# MCU.net
KiCad netlist of a schematic drawn in Altium Designer
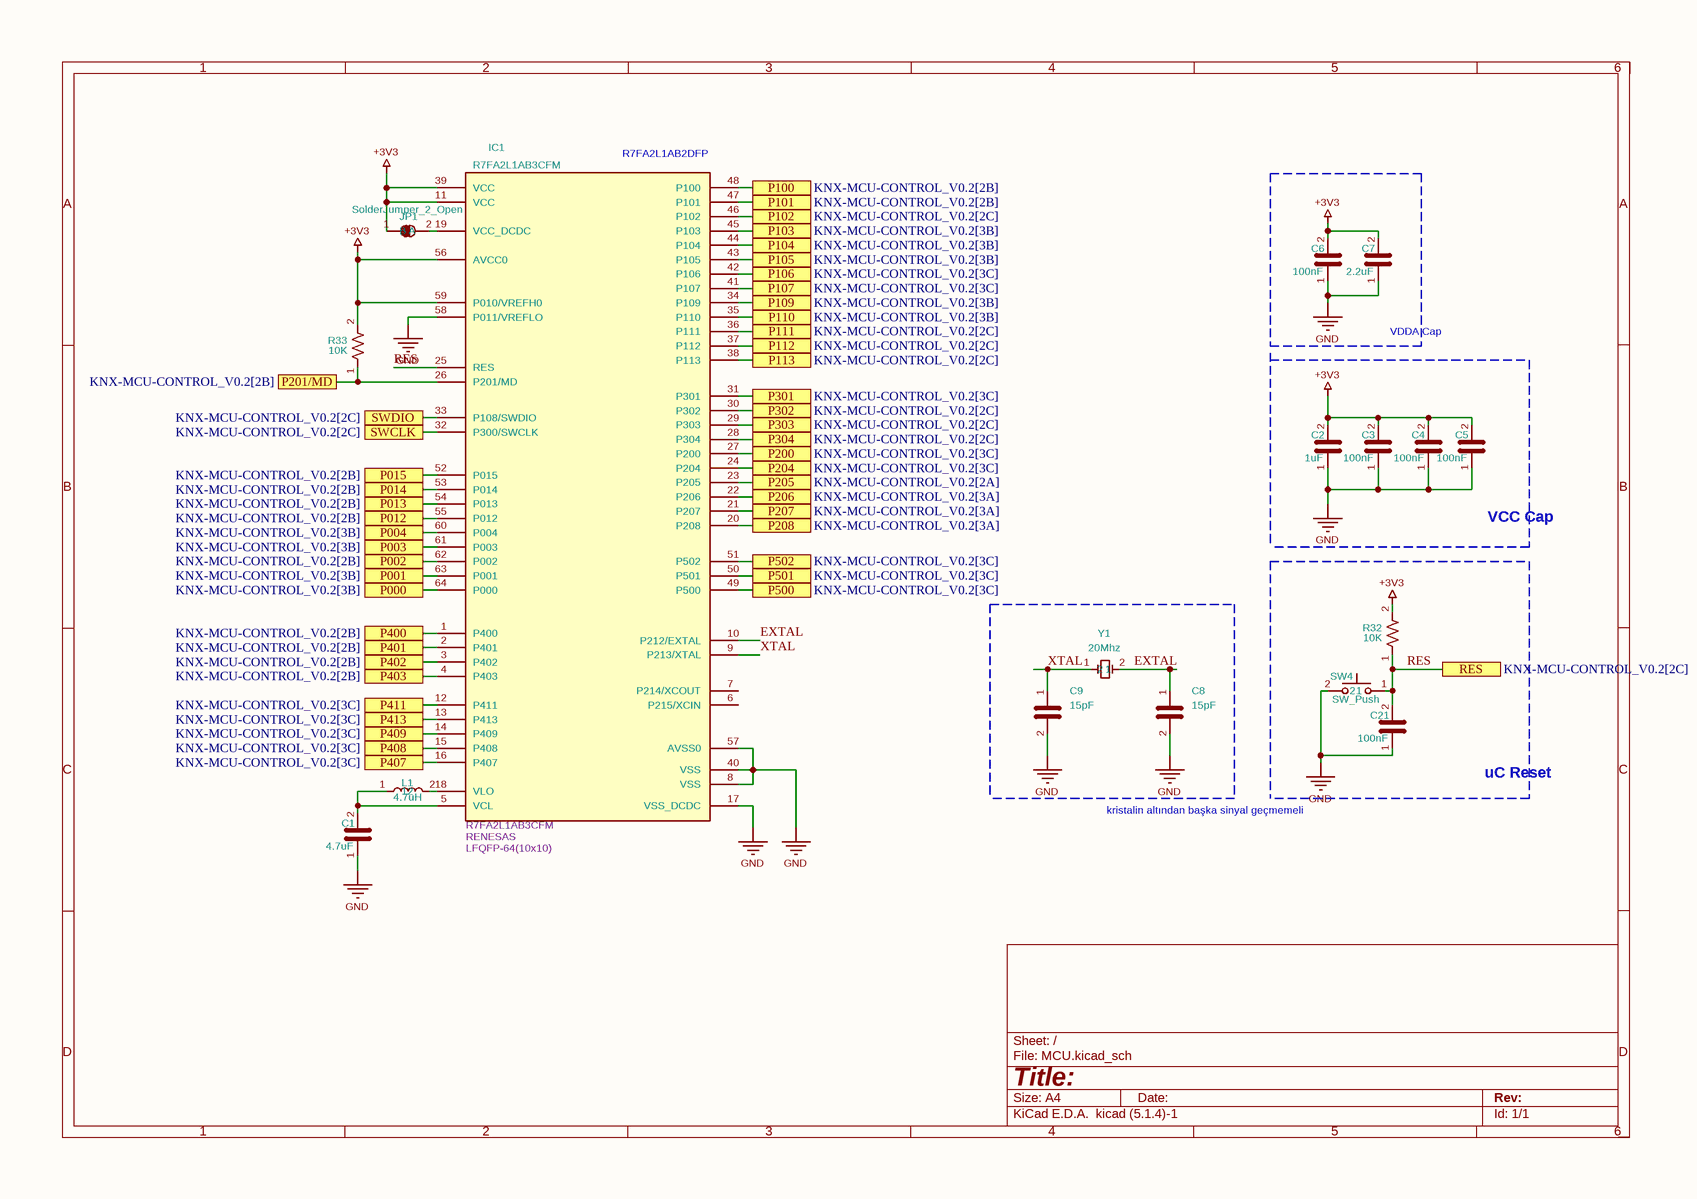
[diagram p0: MCU.SchDoc]

(export (version "E")
  (design (tool "Eeschema 10.0.6"))
  (components
    (comp (ref "C1")
      (value "4.7uF")
      (footprint "C_0603_1608Metric")
      (fields
        (field (name "MANUFACTURER PART NUMBER") "CL10B475KQ8NQNC")
        (field (name "MANUFACTURER") "Samsung Electro-Mechanics")
      )
      (libsource (lib "*") (part "C_3"))
    )
    (comp (ref "C2")
      (value "1uF")
      (footprint "C_0603_1608Metric")
      (fields
        (field (name "MANUFACTURER PART NUMBER") "CL10B105KP8NNNC")
        (field (name "MANUFACTURER") "Samsung Electro-Mechanics")
      )
      (libsource (lib "*") (part "C_3"))
    )
    (comp (ref "C3")
      (value "100nF")
      (footprint "C_0603_1608Metric")
      (fields
        (field (name "MANUFACTURER PART NUMBER") "CC0603KRX7R9BB104")
        (field (name "MANUFACTURER") "YAGEO")
      )
      (libsource (lib "*") (part "C_3"))
    )
    (comp (ref "C4")
      (value "100nF")
      (footprint "C_0603_1608Metric")
      (fields
        (field (name "MANUFACTURER PART NUMBER") "CC0603KRX7R9BB104")
        (field (name "MANUFACTURER") "YAGEO")
      )
      (libsource (lib "*") (part "C_3"))
    )
    (comp (ref "C5")
      (value "100nF")
      (footprint "C_0603_1608Metric")
      (fields
        (field (name "MANUFACTURER PART NUMBER") "CC0603KRX7R9BB104")
        (field (name "MANUFACTURER") "YAGEO")
      )
      (libsource (lib "*") (part "C_3"))
    )
    (comp (ref "C6")
      (value "100nF")
      (footprint "C_0603_1608Metric")
      (fields
        (field (name "MANUFACTURER PART NUMBER") "CC0603KRX7R9BB104")
        (field (name "MANUFACTURER") "YAGEO")
      )
      (libsource (lib "*") (part "C_3"))
    )
    (comp (ref "C7")
      (value "2.2uF")
      (footprint "C_0603_1608Metric")
      (fields
        (field (name "MANUFACTURER PART NUMBER") "CL10B225KP8NNNC")
        (field (name "MANUFACTURER") "Samsung Electro-Mechanics")
      )
      (libsource (lib "*") (part "C_3"))
    )
    (comp (ref "C8")
      (value "15pF")
      (footprint "C_0603_1608Metric")
      (fields
        (field (name "MANUFACTURER PART NUMBER") "CL10C150JB8NNNC")
        (field (name "MANUFACTURER") "Samsung Electro-Mechanics")
      )
      (libsource (lib "SparkFun-Capacitor") (part "20pF_0402_50V_5%"))
    )
    (comp (ref "C9")
      (value "15pF")
      (footprint "C_0603_1608Metric")
      (fields
        (field (name "MANUFACTURER PART NUMBER") "CL10C150JB8NNNC")
        (field (name "MANUFACTURER") "Samsung Electro-Mechanics")
      )
      (libsource (lib "SparkFun-Capacitor") (part "20pF_0402_50V_5%"))
    )
    (comp (ref "C21")
      (value "100nF")
      (footprint "C_0603_1608Metric")
      (fields
        (field (name "MANUFACTURER PART NUMBER") "CC0603KRX7R9BB104")
        (field (name "MANUFACTURER") "YAGEO")
      )
      (libsource (lib "*") (part "C_3"))
    )
    (comp (ref "IC1")
      (value "R7FA2L1AB3CFM")
      (footprint "LQFP-64_10x10mm_P0.5mm")
      (fields
        (field (name "MANUFACTURER PART NUMBER") "R7FA2L1AB3CFM")
        (field (name "MANUFACTURER") "RENESAS")
        (field (name "PACKAGE") "LFQFP-64(10x10)")
      )
      (libsource (lib "Me_Library") (part "R7FA2L1AB3CFM"))
    )
    (comp (ref "JP1")
      (value "SolderJumper_2_Open")
      (footprint "SolderJumper-2_P1.3mm_Open_TrianglePad1.0x1.5mm")
      (libsource (lib "Jumper") (part "SolderJumper_2_Open"))
    )
    (comp (ref "L1")
      (value "4.7uH")
      (footprint "L_APV_ANR5012")
      (fields (field (name "MANUFACTURER") "VIKING") (field (name "MANUFACTURER PART NUMBER") "PCD0302MT4R7"))
      (libsource (lib "Device") (part "L"))
    )
    (comp (ref "R32")
      (value "10K")
      (footprint "R_0603_1608Metric")
      (fields (field (name "MANUFACTURER PART NUMBER") "FRC0603J103TS") (field (name "MANUFACTURER") "FOJAN"))
      (libsource (lib "Device") (part "R_US"))
    )
    (comp (ref "R33")
      (value "10K")
      (footprint "R_0603_1608Metric")
      (fields (field (name "MANUFACTURER PART NUMBER") "FRC0603J103TS") (field (name "MANUFACTURER") "FOJAN"))
      (libsource (lib "Device") (part "R_US"))
    )
    (comp (ref "SW4")
      (value "SW_Push")
      (footprint "SW_SPST_CK_RS282G05A3")
      (description "SWITCH TACTILE SPST 250gf SMD")
      (fields
        (field (name "MANUFACTURER PART NUMBER") "HX 3x6x2.5A-2.5N")
        (field (name "MANUFACTURER") "hanxia")
      )
      (libsource (lib "Switch") (part "SW_Push"))
    )
    (comp (ref "Y1")
      (value "20Mhz")
      (footprint "Crystal_SMD_SeikoEpson_FA238-4Pin_3.2x2.5mm")
      (fields
        (field (name "MANUFACTURER PART NUMBER") "FL3P2X2P5SSC")
        (field (name "MANUFACTURER") "RALTRON")
      )
      (libsource (lib "SparkFun-Clock") (part "Crystal"))
    )
  )
  (nets
    (net (code "1") (name "+3V3") (class "Default")
      (node (ref "C2") (pin "2") (pinfunction "2_2") (pintype "passive"))
      (node (ref "C3") (pin "2") (pinfunction "2_2") (pintype "passive"))
      (node (ref "C4") (pin "2") (pinfunction "2_2") (pintype "passive"))
      (node (ref "C5") (pin "2") (pinfunction "2_2") (pintype "passive"))
      (node (ref "C6") (pin "2") (pinfunction "2_2") (pintype "passive"))
      (node (ref "C7") (pin "2") (pinfunction "2_2") (pintype "passive"))
      (node (ref "IC1") (pin "11") (pinfunction "VCC_11") (pintype "passive"))
      (node (ref "IC1") (pin "39") (pinfunction "VCC_39") (pintype "passive"))
      (node (ref "IC1") (pin "56") (pinfunction "AVCC0_56") (pintype "passive"))
      (node (ref "IC1") (pin "59") (pinfunction "P010/VREFH0_59") (pintype "passive"))
      (node (ref "JP1") (pin "1") (pinfunction "A_1") (pintype "passive"))
      (node (ref "R32") (pin "2") (pinfunction "2_2") (pintype "passive"))
      (node (ref "R33") (pin "2") (pinfunction "2_2") (pintype "passive"))
    )
    (net (code "2") (name "/EXTAL") (class "Default")
      (node (ref "C8") (pin "1") (pinfunction "1_1") (pintype "passive"))
      (node (ref "IC1") (pin "10") (pinfunction "P212/EXTAL_10") (pintype "passive"))
      (node (ref "Y1") (pin "2") (pinfunction "2_2") (pintype "passive"))
    )
    (net (code "3") (name "/P000") (class "Default")
      (node (ref "IC1") (pin "64") (pinfunction "P000_64") (pintype "passive"))
    )
    (net (code "4") (name "/P001") (class "Default")
      (node (ref "IC1") (pin "63") (pinfunction "P001_63") (pintype "passive"))
    )
    (net (code "5") (name "/P002") (class "Default")
      (node (ref "IC1") (pin "62") (pinfunction "P002_62") (pintype "passive"))
    )
    (net (code "6") (name "/P003") (class "Default")
      (node (ref "IC1") (pin "61") (pinfunction "P003_61") (pintype "passive"))
    )
    (net (code "7") (name "/P004") (class "Default")
      (node (ref "IC1") (pin "60") (pinfunction "P004_60") (pintype "passive"))
    )
    (net (code "8") (name "/P012") (class "Default")
      (node (ref "IC1") (pin "55") (pinfunction "P012_55") (pintype "passive"))
    )
    (net (code "9") (name "/P013") (class "Default")
      (node (ref "IC1") (pin "54") (pinfunction "P013_54") (pintype "passive"))
    )
    (net (code "10") (name "/P014") (class "Default")
      (node (ref "IC1") (pin "53") (pinfunction "P014_53") (pintype "passive"))
    )
    (net (code "11") (name "/P015") (class "Default")
      (node (ref "IC1") (pin "52") (pinfunction "P015_52") (pintype "passive"))
    )
    (net (code "12") (name "/P100") (class "Default")
      (node (ref "IC1") (pin "48") (pinfunction "P100_48") (pintype "passive"))
    )
    (net (code "13") (name "/P101") (class "Default")
      (node (ref "IC1") (pin "47") (pinfunction "P101_47") (pintype "passive"))
    )
    (net (code "14") (name "/P102") (class "Default")
      (node (ref "IC1") (pin "46") (pinfunction "P102_46") (pintype "passive"))
    )
    (net (code "15") (name "/P103") (class "Default")
      (node (ref "IC1") (pin "45") (pinfunction "P103_45") (pintype "passive"))
    )
    (net (code "16") (name "/P104") (class "Default")
      (node (ref "IC1") (pin "44") (pinfunction "P104_44") (pintype "passive"))
    )
    (net (code "17") (name "/P105") (class "Default")
      (node (ref "IC1") (pin "43") (pinfunction "P105_43") (pintype "passive"))
    )
    (net (code "18") (name "/P106") (class "Default")
      (node (ref "IC1") (pin "42") (pinfunction "P106_42") (pintype "passive"))
    )
    (net (code "19") (name "/P107") (class "Default")
      (node (ref "IC1") (pin "41") (pinfunction "P107_41") (pintype "passive"))
    )
    (net (code "20") (name "/P109") (class "Default")
      (node (ref "IC1") (pin "34") (pinfunction "P109_34") (pintype "passive"))
    )
    (net (code "21") (name "/P110") (class "Default")
      (node (ref "IC1") (pin "35") (pinfunction "P110_35") (pintype "passive"))
    )
    (net (code "22") (name "/P111") (class "Default")
      (node (ref "IC1") (pin "36") (pinfunction "P111_36") (pintype "passive"))
    )
    (net (code "23") (name "/P112") (class "Default")
      (node (ref "IC1") (pin "37") (pinfunction "P112_37") (pintype "passive"))
    )
    (net (code "24") (name "/P113") (class "Default")
      (node (ref "IC1") (pin "38") (pinfunction "P113_38") (pintype "passive"))
    )
    (net (code "25") (name "/P200") (class "Default")
      (node (ref "IC1") (pin "27") (pinfunction "P200_27") (pintype "passive"))
    )
    (net (code "26") (name "/P201{slash}MD") (class "Default")
      (node (ref "IC1") (pin "26") (pinfunction "P201/MD_26") (pintype "passive"))
      (node (ref "R33") (pin "1") (pinfunction "1_1") (pintype "passive"))
    )
    (net (code "27") (name "/P204") (class "Default")
      (node (ref "IC1") (pin "24") (pinfunction "P204_24") (pintype "passive"))
    )
    (net (code "28") (name "/P205") (class "Default")
      (node (ref "IC1") (pin "23") (pinfunction "P205_23") (pintype "passive"))
    )
    (net (code "29") (name "/P206") (class "Default")
      (node (ref "IC1") (pin "22") (pinfunction "P206_22") (pintype "passive"))
    )
    (net (code "30") (name "/P207") (class "Default")
      (node (ref "IC1") (pin "21") (pinfunction "P207_21") (pintype "passive"))
    )
    (net (code "31") (name "/P208") (class "Default")
      (node (ref "IC1") (pin "20") (pinfunction "P208_20") (pintype "passive"))
    )
    (net (code "32") (name "/P301") (class "Default")
      (node (ref "IC1") (pin "31") (pinfunction "P301_31") (pintype "passive"))
    )
    (net (code "33") (name "/P302") (class "Default")
      (node (ref "IC1") (pin "30") (pinfunction "P302_30") (pintype "passive"))
    )
    (net (code "34") (name "/P303") (class "Default")
      (node (ref "IC1") (pin "29") (pinfunction "P303_29") (pintype "passive"))
    )
    (net (code "35") (name "/P304") (class "Default")
      (node (ref "IC1") (pin "28") (pinfunction "P304_28") (pintype "passive"))
    )
    (net (code "36") (name "/P400") (class "Default")
      (node (ref "IC1") (pin "1") (pinfunction "P400_1") (pintype "passive"))
    )
    (net (code "37") (name "/P401") (class "Default")
      (node (ref "IC1") (pin "2") (pinfunction "P401_2") (pintype "passive"))
    )
    (net (code "38") (name "/P402") (class "Default")
      (node (ref "IC1") (pin "3") (pinfunction "P402_3") (pintype "passive"))
    )
    (net (code "39") (name "/P403") (class "Default")
      (node (ref "IC1") (pin "4") (pinfunction "P403_4") (pintype "passive"))
    )
    (net (code "40") (name "/P407") (class "Default")
      (node (ref "IC1") (pin "16") (pinfunction "P407_16") (pintype "passive"))
    )
    (net (code "41") (name "/P408") (class "Default")
      (node (ref "IC1") (pin "15") (pinfunction "P408_15") (pintype "passive"))
    )
    (net (code "42") (name "/P409") (class "Default")
      (node (ref "IC1") (pin "14") (pinfunction "P409_14") (pintype "passive"))
    )
    (net (code "43") (name "/P411") (class "Default")
      (node (ref "IC1") (pin "12") (pinfunction "P411_12") (pintype "passive"))
    )
    (net (code "44") (name "/P413") (class "Default")
      (node (ref "IC1") (pin "13") (pinfunction "P413_13") (pintype "passive"))
    )
    (net (code "45") (name "/P500") (class "Default")
      (node (ref "IC1") (pin "49") (pinfunction "P500_49") (pintype "passive"))
    )
    (net (code "46") (name "/P501") (class "Default")
      (node (ref "IC1") (pin "50") (pinfunction "P501_50") (pintype "passive"))
    )
    (net (code "47") (name "/P502") (class "Default")
      (node (ref "IC1") (pin "51") (pinfunction "P502_51") (pintype "passive"))
    )
    (net (code "48") (name "/RES") (class "Default")
      (node (ref "C21") (pin "2") (pinfunction "2_2") (pintype "passive"))
      (node (ref "IC1") (pin "25") (pinfunction "RES_25") (pintype "passive"))
      (node (ref "R32") (pin "1") (pinfunction "1_1") (pintype "passive"))
      (node (ref "SW4") (pin "1") (pinfunction "1_1") (pintype "passive"))
    )
    (net (code "49") (name "/SWCLK") (class "Default")
      (node (ref "IC1") (pin "32") (pinfunction "P300/SWCLK_32") (pintype "passive"))
    )
    (net (code "50") (name "/SWDIO") (class "Default")
      (node (ref "IC1") (pin "33") (pinfunction "P108/SWDIO_33") (pintype "passive"))
    )
    (net (code "51") (name "/XTAL") (class "Default")
      (node (ref "C9") (pin "1") (pinfunction "1_1") (pintype "passive"))
      (node (ref "IC1") (pin "9") (pinfunction "P213/XTAL_9") (pintype "passive"))
      (node (ref "Y1") (pin "1") (pinfunction "1_1") (pintype "passive"))
    )
    (net (code "52") (name "GND") (class "Default")
      (node (ref "C1") (pin "1") (pinfunction "1_1") (pintype "passive"))
      (node (ref "C2") (pin "1") (pinfunction "1_1") (pintype "passive"))
      (node (ref "C21") (pin "1") (pinfunction "1_1") (pintype "passive"))
      (node (ref "C3") (pin "1") (pinfunction "1_1") (pintype "passive"))
      (node (ref "C4") (pin "1") (pinfunction "1_1") (pintype "passive"))
      (node (ref "C5") (pin "1") (pinfunction "1_1") (pintype "passive"))
      (node (ref "C6") (pin "1") (pinfunction "1_1") (pintype "passive"))
      (node (ref "C7") (pin "1") (pinfunction "1_1") (pintype "passive"))
      (node (ref "C8") (pin "2") (pinfunction "2_2") (pintype "passive"))
      (node (ref "C9") (pin "2") (pinfunction "2_2") (pintype "passive"))
      (node (ref "IC1") (pin "17") (pinfunction "VSS_DCDC_17") (pintype "passive"))
      (node (ref "IC1") (pin "40") (pinfunction "VSS_40") (pintype "passive"))
      (node (ref "IC1") (pin "57") (pinfunction "AVSS0_57") (pintype "passive"))
      (node (ref "IC1") (pin "58") (pinfunction "P011/VREFLO_58") (pintype "passive"))
      (node (ref "IC1") (pin "8") (pinfunction "VSS_8") (pintype "passive"))
      (node (ref "SW4") (pin "2") (pinfunction "2_2") (pintype "passive"))
    )
    (net (code "53") (name "Net-(IC1-VCC_DCDC)") (class "Default")
      (node (ref "IC1") (pin "19") (pinfunction "VCC_DCDC_19") (pintype "passive"))
      (node (ref "JP1") (pin "2") (pinfunction "B_2") (pintype "passive"))
    )
    (net (code "54") (name "Net-(IC1-VCL)") (class "Default")
      (node (ref "C1") (pin "2") (pinfunction "2_2") (pintype "passive"))
      (node (ref "IC1") (pin "5") (pinfunction "VCL_5") (pintype "passive"))
      (node (ref "L1") (pin "1") (pinfunction "1_1") (pintype "passive"))
    )
    (net (code "55") (name "Net-(IC1-VLO)") (class "Default")
      (node (ref "IC1") (pin "18") (pinfunction "VLO_18") (pintype "passive"))
      (node (ref "L1") (pin "2") (pinfunction "2_2") (pintype "passive"))
    )
    (net (code "56") (name "unconnected-(IC1-P214{slash}XCOUT-Pad7)") (class "Default")
      (node (ref "IC1") (pin "7") (pinfunction "P214/XCOUT_7") (pintype "passive"))
    )
    (net (code "57") (name "unconnected-(IC1-P215{slash}XCIN-Pad6)") (class "Default")
      (node (ref "IC1") (pin "6") (pinfunction "P215/XCIN_6") (pintype "passive"))
    )
  )
)
